# Lab4.net
KiCad netlist of a schematic drawn in EAGLE
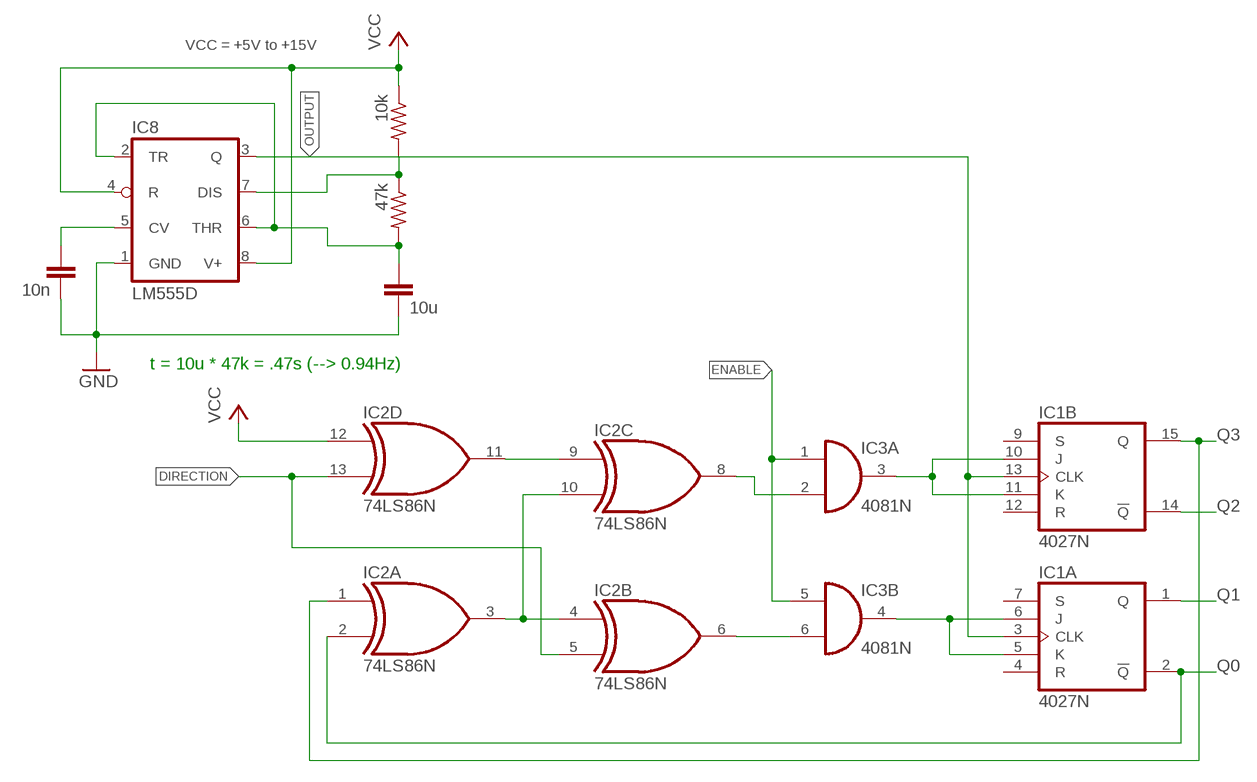
[diagram p0: schematic, sheet 1]

(export (version "E")
  (design (tool "Eeschema 10.0.6"))
  (components
    (comp (ref "C7")
      (value "10u")
      (footprint "eagle-import:C0805")
      (libsource (lib "eagle-import") (part "C-EUC0805"))
    )
    (comp (ref "C8")
      (value "10n")
      (footprint "eagle-import:C0805")
      (libsource (lib "eagle-import") (part "C-EUC0805"))
    )
    (comp (ref "IC1")
      (value "4027N")
      (footprint "eagle-import:DIL16")
      (libsource (lib "eagle-import") (part "4027N"))
    )
    (comp (ref "IC2")
      (value "74LS86N")
      (footprint "eagle-import:DIL14")
      (libsource (lib "eagle-import") (part "7486NLS"))
    )
    (comp (ref "IC3")
      (value "4081N")
      (footprint "eagle-import:DIL14")
      (libsource (lib "eagle-import") (part "4081N"))
    )
    (comp (ref "IC8")
      (value "LM555D")
      (footprint "eagle-import:SO08")
      (libsource (lib "eagle-import") (part "555DLM"))
    )
    (comp (ref "RA3")
      (value "10k")
      (footprint "eagle-import:R0805")
      (libsource (lib "eagle-import") (part "R-US_R0805"))
    )
    (comp (ref "RB1")
      (value "47k")
      (footprint "eagle-import:R0805")
      (libsource (lib "eagle-import") (part "R-US_R0805"))
    )
  )
  (nets
    (net (code "1") (name "/Q0") (class "Default")
      (node (ref "IC1") (pin "2") (pinfunction "~{Q}_2") (pintype "output"))
      (node (ref "IC2") (pin "2") (pinfunction "I1_2") (pintype "input"))
    )
    (net (code "2") (name "/Q1") (class "Default")
      (node (ref "IC1") (pin "1") (pinfunction "Q_1") (pintype "output"))
    )
    (net (code "3") (name "/Q2") (class "Default")
      (node (ref "IC1") (pin "14") (pinfunction "~{Q}_14") (pintype "output"))
    )
    (net (code "4") (name "/Q3") (class "Default")
      (node (ref "IC1") (pin "15") (pinfunction "Q_15") (pintype "output"))
      (node (ref "IC2") (pin "1") (pinfunction "I0_1") (pintype "input"))
    )
    (net (code "5") (name "DIRECTION") (class "Default")
      (node (ref "IC2") (pin "13") (pinfunction "I1_13") (pintype "input"))
      (node (ref "IC2") (pin "5") (pinfunction "I1_5") (pintype "input"))
    )
    (net (code "6") (name "ENABLE") (class "Default")
      (node (ref "IC3") (pin "1") (pinfunction "I0_1") (pintype "input"))
      (node (ref "IC3") (pin "5") (pinfunction "I0_5") (pintype "input"))
    )
    (net (code "7") (name "GND") (class "Default")
      (node (ref "C7") (pin "2") (pinfunction "2_2") (pintype "passive"))
      (node (ref "C8") (pin "2") (pinfunction "2_2") (pintype "passive"))
      (node (ref "IC8") (pin "1") (pinfunction "GND_1") (pintype "power_in"))
    )
    (net (code "8") (name "Net-(IC1A-J)") (class "Default")
      (node (ref "IC1") (pin "5") (pinfunction "K_5") (pintype "input"))
      (node (ref "IC1") (pin "6") (pinfunction "J_6") (pintype "input"))
      (node (ref "IC3") (pin "4") (pinfunction "O_4") (pintype "output"))
    )
    (net (code "9") (name "Net-(IC1B-J)") (class "Default")
      (node (ref "IC1") (pin "10") (pinfunction "J_10") (pintype "input"))
      (node (ref "IC1") (pin "11") (pinfunction "K_11") (pintype "input"))
      (node (ref "IC3") (pin "3") (pinfunction "O_3") (pintype "output"))
    )
    (net (code "10") (name "Net-(IC2A-O)") (class "Default")
      (node (ref "IC2") (pin "10") (pinfunction "I1_10") (pintype "input"))
      (node (ref "IC2") (pin "3") (pinfunction "O_3") (pintype "output"))
      (node (ref "IC2") (pin "4") (pinfunction "I0_4") (pintype "input"))
    )
    (net (code "11") (name "Net-(IC2B-O)") (class "Default")
      (node (ref "IC2") (pin "6") (pinfunction "O_6") (pintype "output"))
      (node (ref "IC3") (pin "6") (pinfunction "I1_6") (pintype "input"))
    )
    (net (code "12") (name "Net-(IC2C-I0)") (class "Default")
      (node (ref "IC2") (pin "11") (pinfunction "O_11") (pintype "output"))
      (node (ref "IC2") (pin "9") (pinfunction "I0_9") (pintype "input"))
    )
    (net (code "13") (name "Net-(IC2C-O)") (class "Default")
      (node (ref "IC2") (pin "8") (pinfunction "O_8") (pintype "output"))
      (node (ref "IC3") (pin "2") (pinfunction "I1_2") (pintype "input"))
    )
    (net (code "14") (name "Net-(IC8-CV)") (class "Default")
      (node (ref "C8") (pin "1") (pinfunction "1_1") (pintype "passive"))
      (node (ref "IC8") (pin "5") (pinfunction "CV_5") (pintype "input"))
    )
    (net (code "15") (name "Net-(IC8-DIS)") (class "Default")
      (node (ref "IC8") (pin "7") (pinfunction "DIS_7") (pintype "input"))
      (node (ref "RA3") (pin "2") (pinfunction "2_2") (pintype "passive"))
      (node (ref "RB1") (pin "1") (pinfunction "1_1") (pintype "passive"))
    )
    (net (code "16") (name "Net-(IC8-THR)") (class "Default")
      (node (ref "C7") (pin "1") (pinfunction "1_1") (pintype "passive"))
      (node (ref "IC8") (pin "2") (pinfunction "TR_2") (pintype "input"))
      (node (ref "IC8") (pin "6") (pinfunction "THR_6") (pintype "input"))
      (node (ref "RB1") (pin "2") (pinfunction "2_2") (pintype "passive"))
    )
    (net (code "17") (name "OUTPUT") (class "Default")
      (node (ref "IC1") (pin "13") (pinfunction "CLK_13") (pintype "input"))
      (node (ref "IC1") (pin "3") (pinfunction "CLK_3") (pintype "input"))
      (node (ref "IC8") (pin "3") (pinfunction "Q_3") (pintype "output"))
    )
    (net (code "18") (name "VCC") (class "Default")
      (node (ref "IC2") (pin "12") (pinfunction "I0_12") (pintype "input"))
      (node (ref "IC8") (pin "4") (pinfunction "R_4") (pintype "input"))
      (node (ref "IC8") (pin "8") (pinfunction "V+_8") (pintype "power_in"))
      (node (ref "RA3") (pin "1") (pinfunction "1_1") (pintype "passive"))
    )
    (net (code "19") (name "unconnected-(IC1A-R-Pad4)") (class "Default")
      (node (ref "IC1") (pin "4") (pinfunction "R_4") (pintype "input"))
    )
    (net (code "20") (name "unconnected-(IC1A-S-Pad7)") (class "Default")
      (node (ref "IC1") (pin "7") (pinfunction "S_7") (pintype "input"))
    )
    (net (code "21") (name "unconnected-(IC1B-R-Pad12)") (class "Default")
      (node (ref "IC1") (pin "12") (pinfunction "R_12") (pintype "input"))
    )
    (net (code "22") (name "unconnected-(IC1B-S-Pad9)") (class "Default")
      (node (ref "IC1") (pin "9") (pinfunction "S_9") (pintype "input"))
    )
  )
)
